# MOSFET_based_switching_circuit.net
KiCad netlist of a schematic drawn in Altium Designer
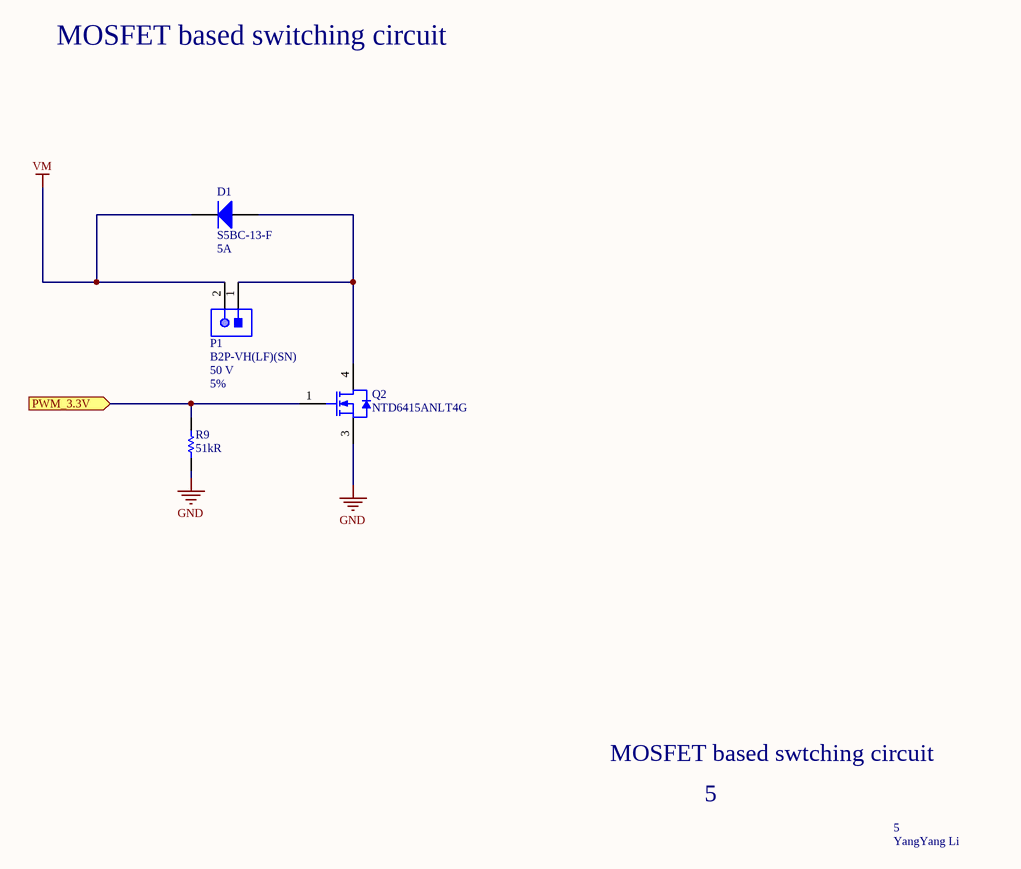
[diagram p0: MOSFET_based_switching_circuit.SchDoc]

(export (version "E")
  (design (tool "Eeschema 10.0.6"))
  (components
    (comp (ref "D1")
      (value "S5BC-13-F")
      (footprint "DIOD-S5xC_V")
      (fields (field (name "MANUFACTURER") "Diodes Inc") (field (name "AVERAGE RECTIFIED CURRENT-MAX") "5A"))
      (libsource (lib "Altium Content Vault") (part "D-AK-2"))
    )
    (comp (ref "P1")
      (value "B2P-VH(LF)(SN)")
      (footprint "JST-B2P-VH(LF)(SN)_V")
      (fields (field (name "VOLTAGE RATING") "50 V") (field (name "TOLERANCE") "5%"))
      (libsource (lib "Altium Content Vault") (part "CN-1P-M-R2"))
    )
    (comp (ref "Q2")
      (value "NTD6415ANLT4G")
      (footprint "ONSC-DPAK-3-369AA-01_V")
      (description "N-Channel Power MOSFET, 100 V, 23 A, 56 mOhm, 3-Pin DPAK, Pb-Free, Tape and Reel")
      (fields (field (name "MANUFACTURER") "On Semiconductor"))
      (libsource (lib "Altium Content Vault") (part "ONSC-NMOS-G1S3D4-3_B"))
    )
    (comp (ref "R9")
      (value "51kR")
      (footprint "RESC3216X60X45NL10T20")
      (description "CRCW120651K0JNEA")
      (fields (field (name "MANUFACTURER") "Vishay Dale"))
      (libsource (lib "Altium Content Vault") (part "RES"))
    )
  )
  (nets
    (net (code "1") (name "/PWM_3.3V") (class "Default")
      (node (ref "Q2") (pin "1") (pinfunction "G_1") (pintype "passive"))
      (node (ref "R9") (pin "2") (pinfunction "2_2") (pintype "passive"))
    )
    (net (code "2") (name "GND") (class "Default")
      (node (ref "Q2") (pin "3") (pinfunction "S_3") (pintype "passive"))
      (node (ref "R9") (pin "1") (pinfunction "1_1") (pintype "passive"))
    )
    (net (code "3") (name "Net-(D1-A)") (class "Default")
      (node (ref "D1") (pin "1") (pinfunction "A_1") (pintype "passive"))
      (node (ref "P1") (pin "1") (pinfunction "1_1") (pintype "passive"))
      (node (ref "Q2") (pin "4") (pinfunction "D_4") (pintype "passive"))
    )
    (net (code "4") (name "VM") (class "Default")
      (node (ref "D1") (pin "2") (pinfunction "K_2") (pintype "passive"))
      (node (ref "P1") (pin "2") (pinfunction "2_2") (pintype "passive"))
    )
  )
)
